# SCH_led-chaser_2025-03-19.net
KiCad netlist of a schematic drawn in EasyEDA
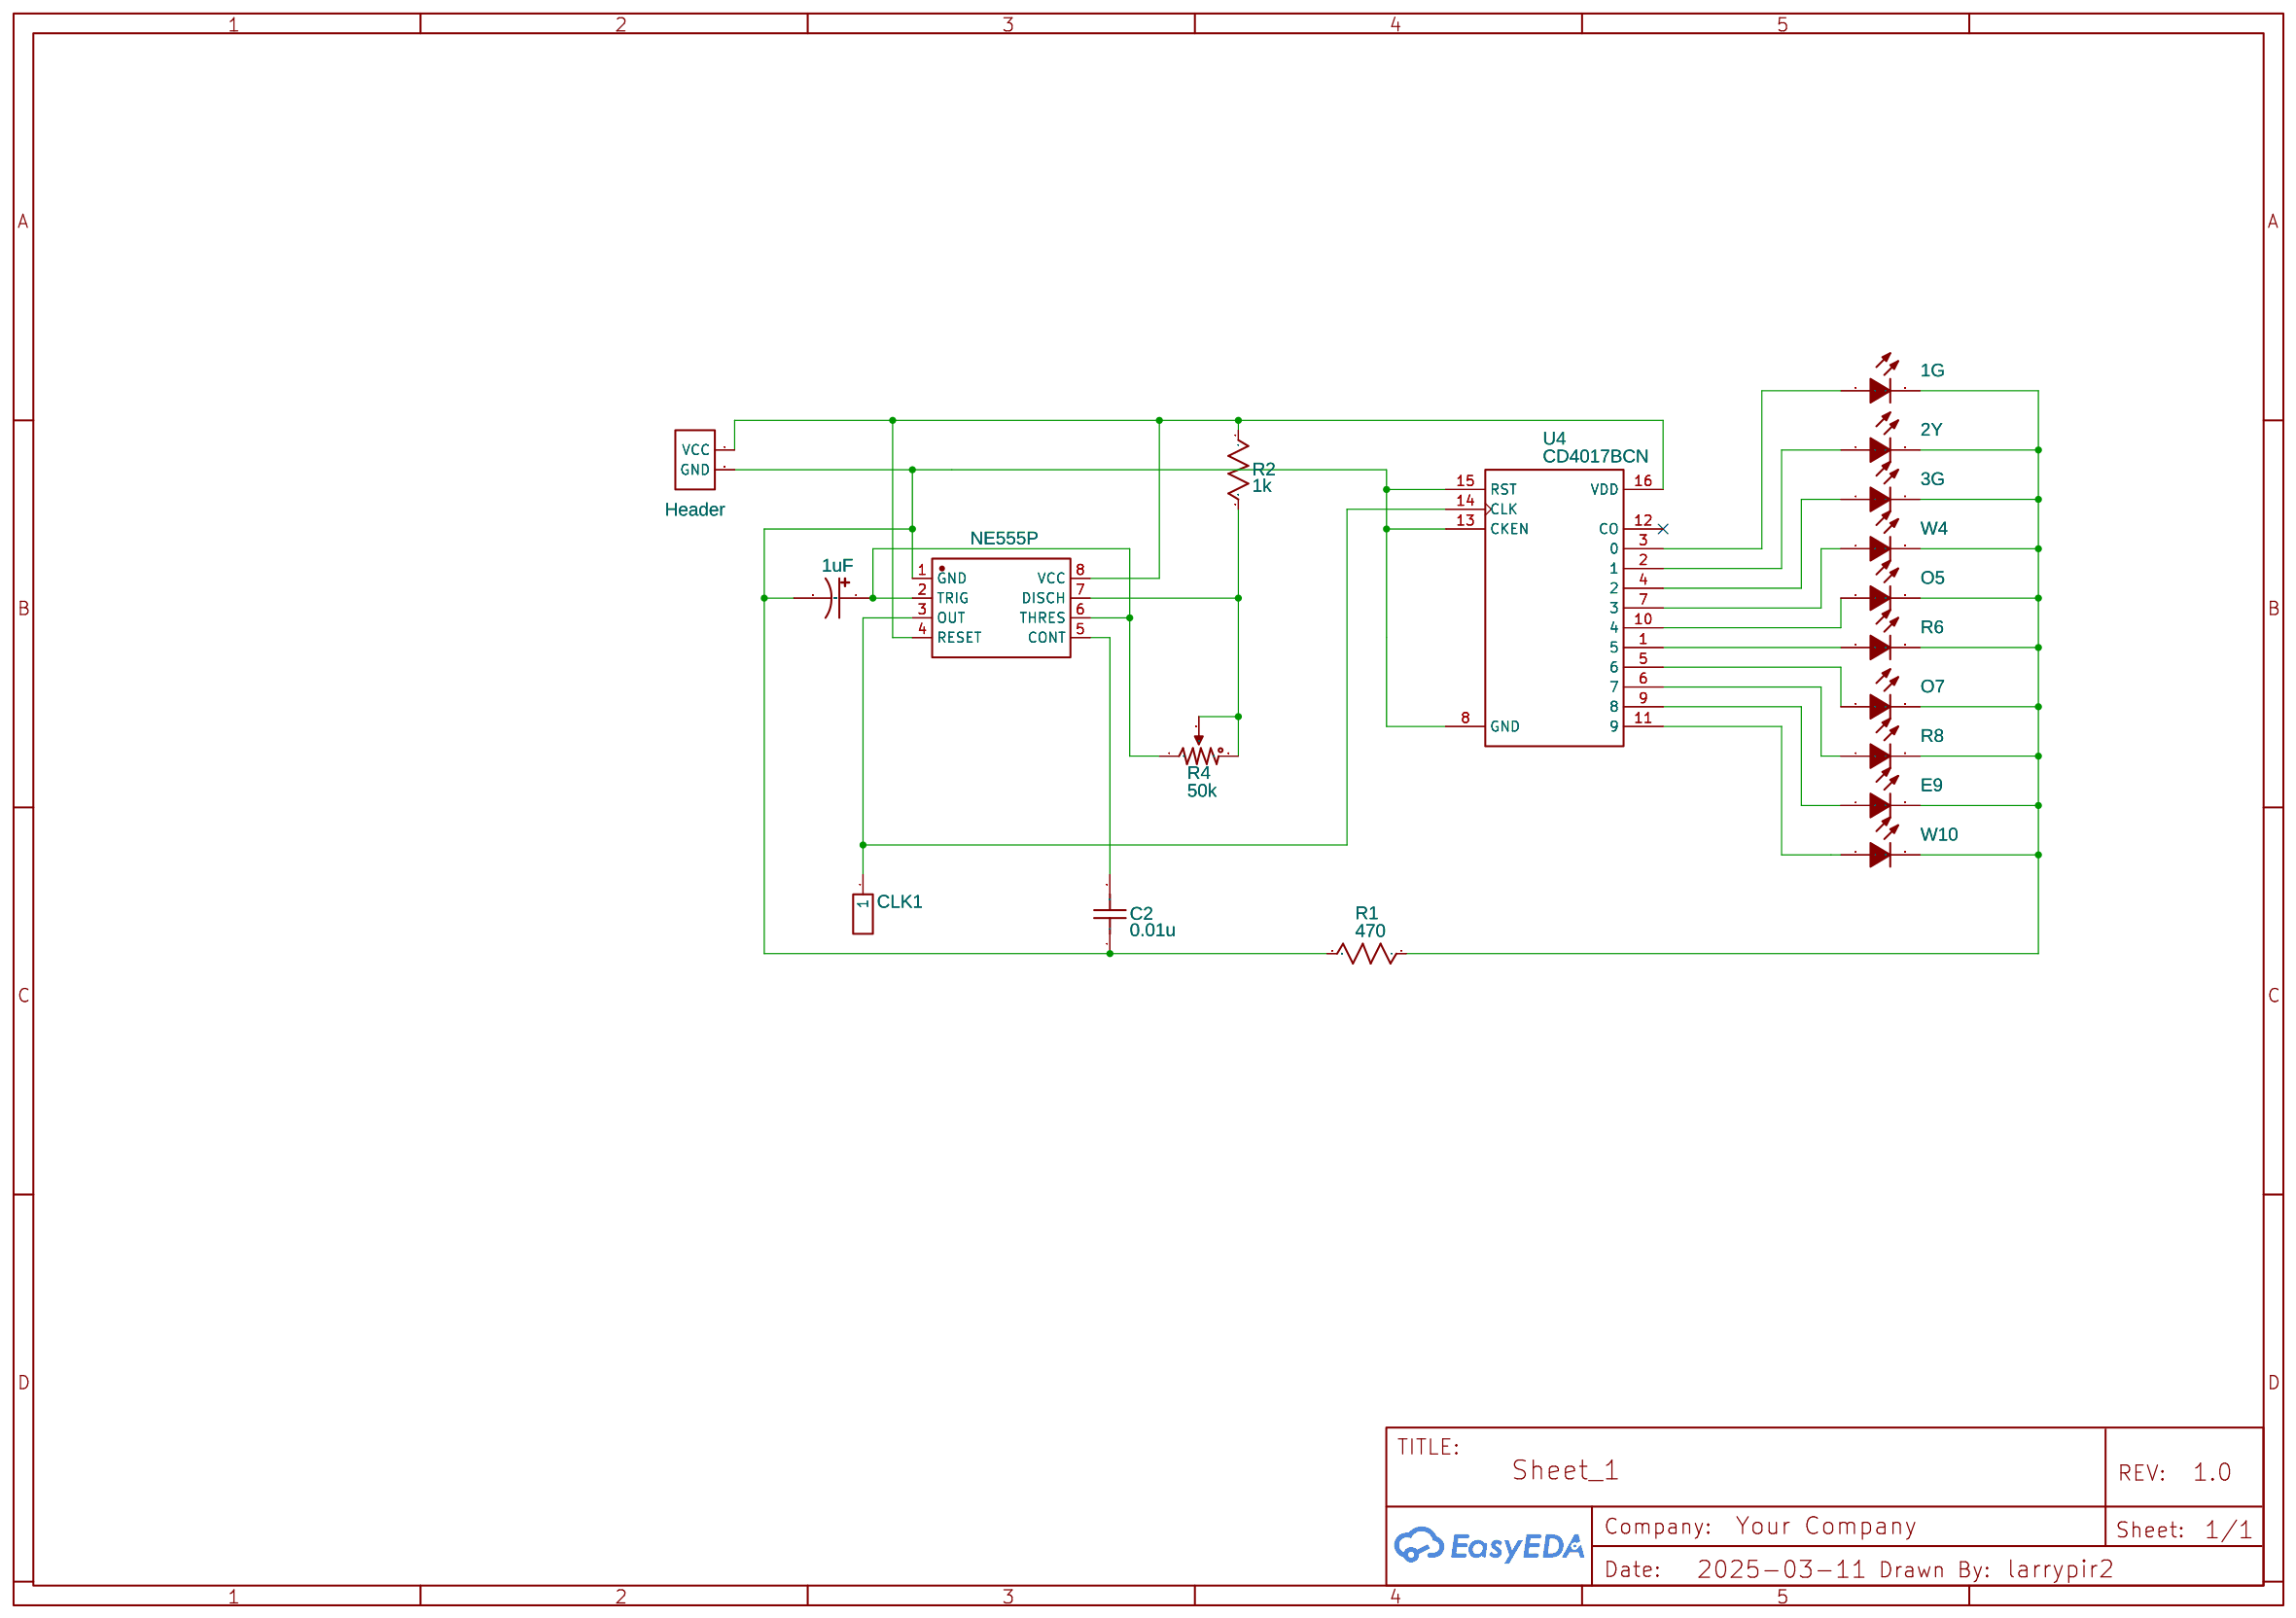
[diagram p0: schematic sheet]

(export (version "E")
  (design (tool "Eeschema 10.0.6"))
  (components
    (comp (ref "1G") (value "LED_5MM") (libsource (lib "") (part "LED_5MM_5")))
    (comp (ref "2Y") (value "LED_5MM") (libsource (lib "") (part "LED_5MM_3")))
    (comp (ref "3G") (value "LED_5MM") (libsource (lib "") (part "LED_5MM")))
    (comp (ref "C1")
      (value "1uF")
      (fields (field (name "Manufacturer Part") "UVZ1H010MDD") (field (name "Manufacturer") "Nichicon(尼吉康)"))
      (libsource (lib "") (part "UVZ1H010MDD"))
    )
    (comp (ref "C2") (value "0.01u") (libsource (lib "") (part "C_0603_US")))
    (comp (ref "CLK1")
      (value "C81276")
      (fields
        (field (name "Manufacturer Part") "2.54-1*1P针")
        (field (name "Manufacturer") "BOOMELE(Boom Precision Elec)")
      )
      (libsource (lib "") (part "Header-Male-2.54_1x1"))
    )
    (comp (ref "E9") (value "LED_5MM") (libsource (lib "") (part "LED_5MM_1")))
    (comp (ref "H1") (value "Header") (libsource (lib "") (part "HEADER-FEMALE-2.54_1X2")))
    (comp (ref "O5") (value "LED_5MM") (libsource (lib "") (part "LED_5MM_6")))
    (comp (ref "O7") (value "LED_5MM") (libsource (lib "") (part "LED_5MM_6")))
    (comp (ref "R1")
      (value "470")
      (fields (field (name "Manufacturer Part") "?"))
      (libsource (lib "") (part "Resistor_1"))
    )
    (comp (ref "R2")
      (value "1k")
      (fields (field (name "Manufacturer Part") "?"))
      (libsource (lib "") (part "Resistor"))
    )
    (comp (ref "R4")
      (value "50k")
      (fields (field (name "Manufacturer Part") "?"))
      (libsource (lib "") (part "Potentiometer"))
    )
    (comp (ref "R6") (value "LED_5MM") (libsource (lib "") (part "LED_5MM_2")))
    (comp (ref "R8") (value "LED_5MM") (libsource (lib "") (part "LED_5MM_2")))
    (comp (ref "U2")
      (value "NE555P")
      (fields (field (name "Manufacturer") "TI(德州仪器)"))
      (libsource (lib "") (part "NE555P"))
    )
    (comp (ref "U4") (value "CD4017BCN") (libsource (lib "") (part "CD4017BCN")))
    (comp (ref "W4") (value "LED_5MM") (libsource (lib "") (part "LED_5MM_4")))
    (comp (ref "W10") (value "LED_5MM") (libsource (lib "") (part "LED_5MM_4")))
  )
  (nets
    (net (code "1") (name "Net-(1G-A)") (class "Default")
      (node (ref "1G") (pin "1") (pinfunction "A_1") (pintype "input"))
      (node (ref "U4") (pin "3") (pinfunction "0_3") (pintype "output"))
    )
    (net (code "2") (name "Net-(1G-K)") (class "Default")
      (node (ref "1G") (pin "2") (pinfunction "K_2") (pintype "input"))
      (node (ref "2Y") (pin "2") (pinfunction "K_2") (pintype "input"))
      (node (ref "3G") (pin "2") (pinfunction "K_2") (pintype "input"))
      (node (ref "E9") (pin "2") (pinfunction "K_2") (pintype "input"))
      (node (ref "O5") (pin "2") (pinfunction "K_2") (pintype "input"))
      (node (ref "O7") (pin "2") (pinfunction "K_2") (pintype "input"))
      (node (ref "R1") (pin "1") (pinfunction "1_1") (pintype "unspecified"))
      (node (ref "R6") (pin "2") (pinfunction "K_2") (pintype "input"))
      (node (ref "R8") (pin "2") (pinfunction "K_2") (pintype "input"))
      (node (ref "W10") (pin "2") (pinfunction "K_2") (pintype "input"))
      (node (ref "W4") (pin "2") (pinfunction "K_2") (pintype "input"))
    )
    (net (code "3") (name "Net-(2Y-A)") (class "Default")
      (node (ref "2Y") (pin "1") (pinfunction "A_1") (pintype "input"))
      (node (ref "U4") (pin "2") (pinfunction "1_2") (pintype "output"))
    )
    (net (code "4") (name "Net-(3G-A)") (class "Default")
      (node (ref "3G") (pin "1") (pinfunction "A_1") (pintype "input"))
      (node (ref "U4") (pin "4") (pinfunction "2_4") (pintype "output"))
    )
    (net (code "5") (name "Net-(E9-A)") (class "Default")
      (node (ref "E9") (pin "1") (pinfunction "A_1") (pintype "input"))
      (node (ref "U4") (pin "9") (pinfunction "8_9") (pintype "output"))
    )
    (net (code "6") (name "Net-(H1-GND)") (class "Default")
      (node (ref "C1") (pin "2") (pinfunction "2_2") (pintype "unspecified"))
      (node (ref "C2") (pin "1") (pinfunction "1_1") (pintype "unspecified"))
      (node (ref "H1") (pin "2") (pinfunction "GND_2") (pintype "unspecified"))
      (node (ref "R1") (pin "2") (pinfunction "2_2") (pintype "unspecified"))
      (node (ref "U2") (pin "1") (pinfunction "GND_1") (pintype "unspecified"))
      (node (ref "U4") (pin "13") (pinfunction "CKEN_13") (pintype "unspecified"))
      (node (ref "U4") (pin "15") (pinfunction "RST_15") (pintype "unspecified"))
      (node (ref "U4") (pin "8") (pinfunction "GND_8") (pintype "passive"))
    )
    (net (code "7") (name "Net-(H1-VCC)") (class "Default")
      (node (ref "H1") (pin "1") (pinfunction "VCC_1") (pintype "unspecified"))
      (node (ref "R2") (pin "1") (pinfunction "1_1") (pintype "unspecified"))
      (node (ref "U2") (pin "4") (pinfunction "RESET_4") (pintype "unspecified"))
      (node (ref "U2") (pin "8") (pinfunction "VCC_8") (pintype "unspecified"))
      (node (ref "U4") (pin "16") (pinfunction "VDD_16") (pintype "passive"))
    )
    (net (code "8") (name "Net-(O5-A)") (class "Default")
      (node (ref "O5") (pin "1") (pinfunction "A_1") (pintype "input"))
      (node (ref "U4") (pin "10") (pinfunction "4_10") (pintype "output"))
    )
    (net (code "9") (name "Net-(O7-A)") (class "Default")
      (node (ref "O7") (pin "1") (pinfunction "A_1") (pintype "input"))
      (node (ref "U4") (pin "5") (pinfunction "6_5") (pintype "output"))
    )
    (net (code "10") (name "Net-(R4-2)") (class "Default")
      (node (ref "R2") (pin "2") (pinfunction "2_2") (pintype "unspecified"))
      (node (ref "R4") (pin "2") (pinfunction "3_2") (pintype "unspecified"))
      (node (ref "R4") (pin "3") (pinfunction "2_3") (pintype "unspecified"))
      (node (ref "U2") (pin "7") (pinfunction "DISCH_7") (pintype "unspecified"))
    )
    (net (code "11") (name "Net-(R6-A)") (class "Default")
      (node (ref "R6") (pin "1") (pinfunction "A_1") (pintype "input"))
      (node (ref "U4") (pin "1") (pinfunction "5_1") (pintype "output"))
    )
    (net (code "12") (name "Net-(R8-A)") (class "Default")
      (node (ref "R8") (pin "1") (pinfunction "A_1") (pintype "input"))
      (node (ref "U4") (pin "6") (pinfunction "7_6") (pintype "output"))
    )
    (net (code "13") (name "Net-(U2-CONT)") (class "Default")
      (node (ref "C2") (pin "2") (pinfunction "2_2") (pintype "unspecified"))
      (node (ref "U2") (pin "5") (pinfunction "CONT_5") (pintype "unspecified"))
    )
    (net (code "14") (name "Net-(U2-OUT)") (class "Default")
      (node (ref "CLK1") (pin "1") (pinfunction "1_1") (pintype "unspecified"))
      (node (ref "U2") (pin "3") (pinfunction "OUT_3") (pintype "unspecified"))
      (node (ref "U4") (pin "14") (pinfunction "CLK_14") (pintype "unspecified"))
    )
    (net (code "15") (name "Net-(U2-THRES)") (class "Default")
      (node (ref "C1") (pin "1") (pinfunction "1_1") (pintype "unspecified"))
      (node (ref "R4") (pin "1") (pinfunction "1_1") (pintype "unspecified"))
      (node (ref "U2") (pin "2") (pinfunction "TRIG_2") (pintype "unspecified"))
      (node (ref "U2") (pin "6") (pinfunction "THRES_6") (pintype "unspecified"))
    )
    (net (code "16") (name "Net-(U4-3)") (class "Default")
      (node (ref "U4") (pin "7") (pinfunction "3_7") (pintype "output"))
      (node (ref "W4") (pin "1") (pinfunction "A_1") (pintype "input"))
    )
    (net (code "17") (name "Net-(U4-9)") (class "Default")
      (node (ref "U4") (pin "11") (pinfunction "9_11") (pintype "output"))
      (node (ref "W10") (pin "1") (pinfunction "A_1") (pintype "input"))
    )
    (net (code "18") (name "unconnected-(U4-CO-Pad12)") (class "Default")
      (node (ref "U4") (pin "12") (pinfunction "CO_12") (pintype "output+no_connect"))
    )
  )
)
